# MicroMod-Ethernet-Function-Board.net
KiCad netlist of a schematic drawn in EAGLE
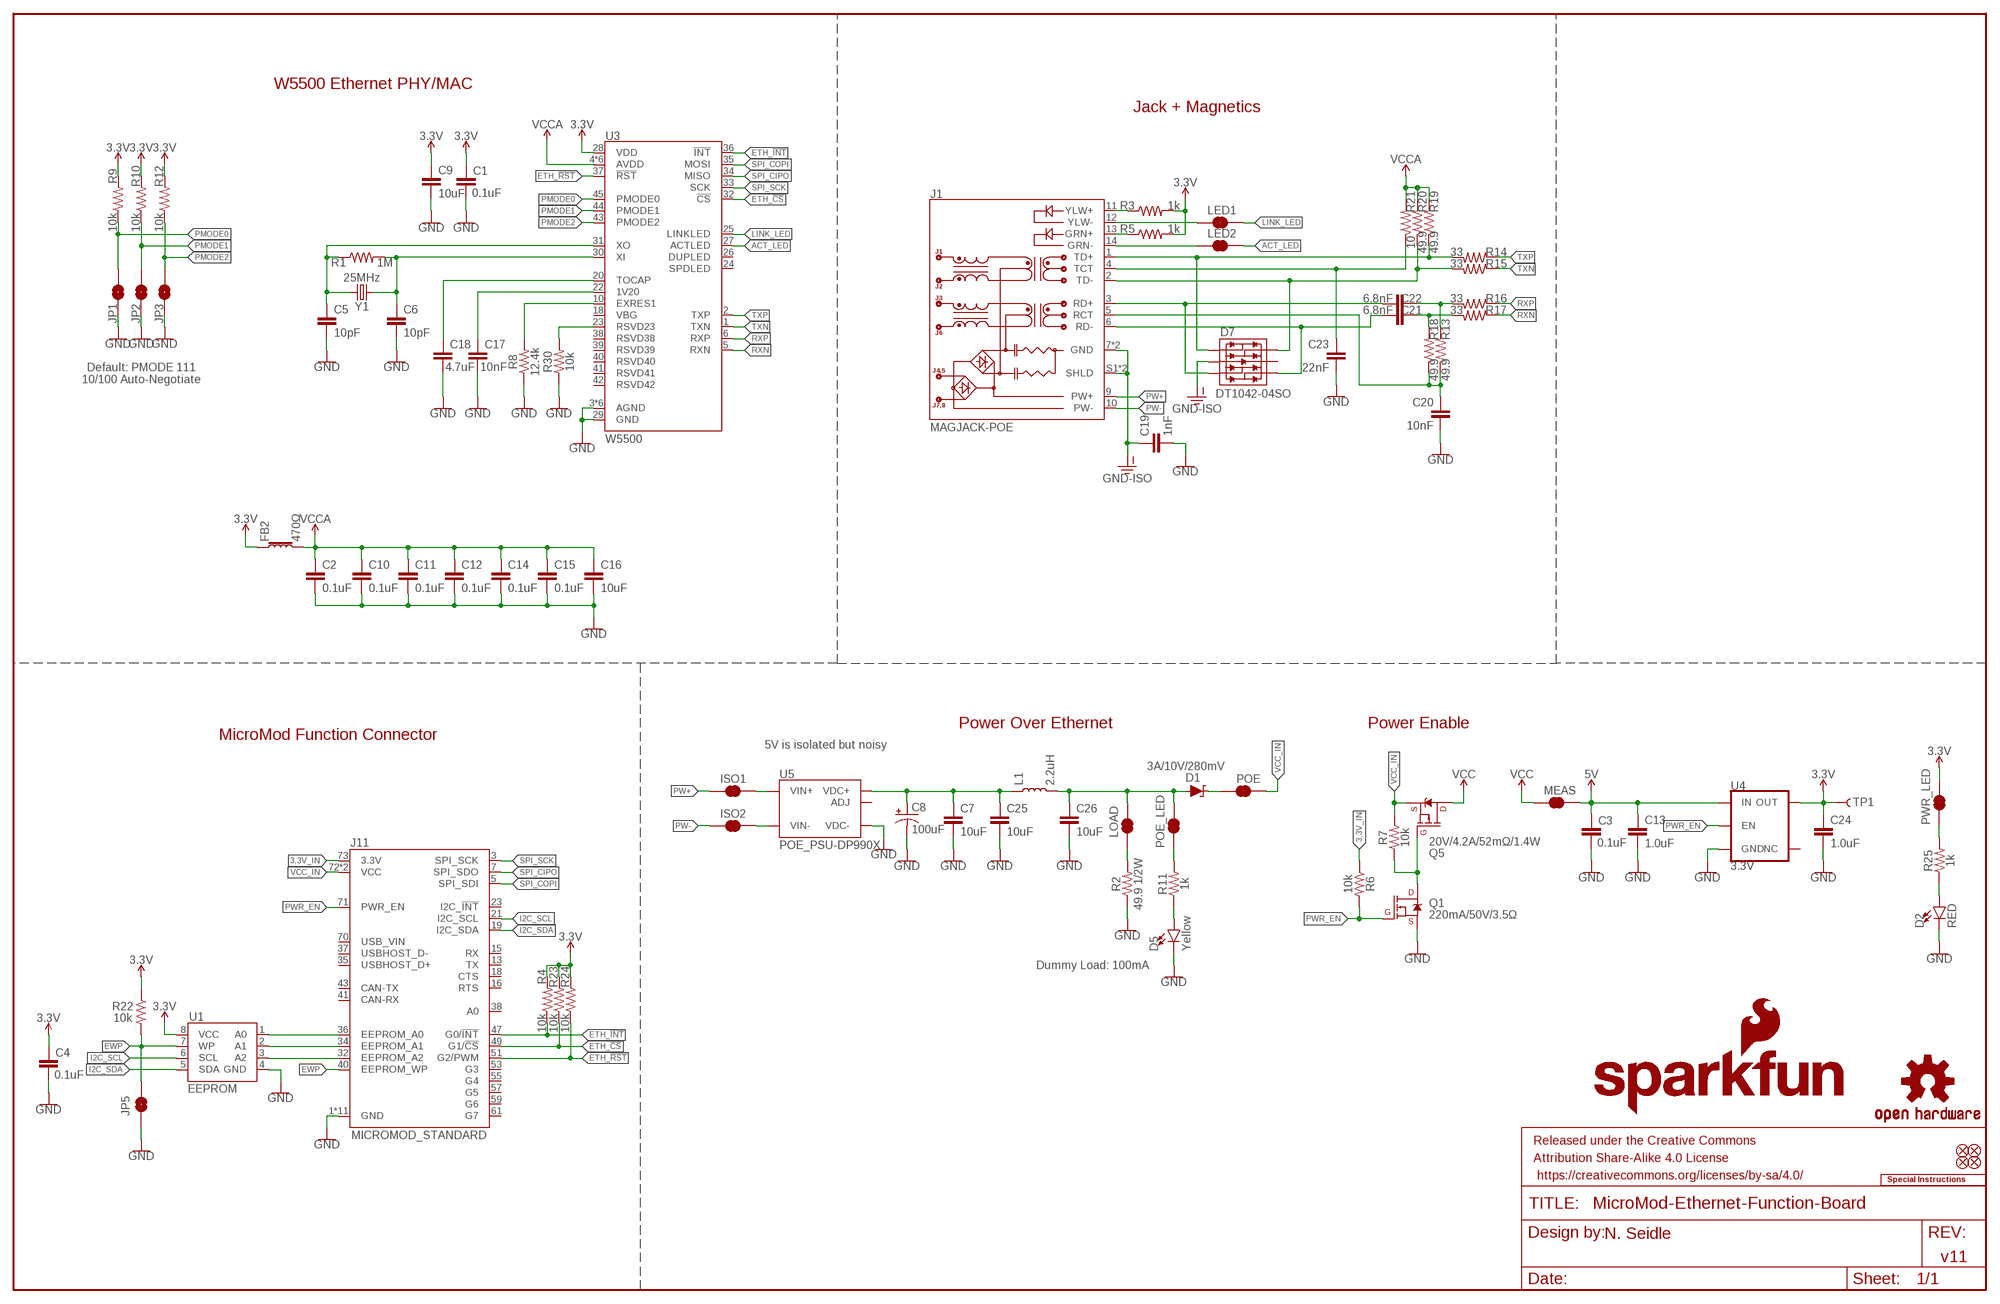
[diagram p0: schematic, sheet 1]

(export (version "E")
  (design (tool "Eeschema 10.0.6"))
  (components
    (comp (ref "C1")
      (value "0.1uF")
      (footprint "eagle-import:0603")
      (libsource (lib "eagle-import") (part "0.1UF-0603-25V-(+80/-20%)"))
    )
    (comp (ref "C2")
      (value "0.1uF")
      (footprint "eagle-import:0603")
      (libsource (lib "eagle-import") (part "0.1UF-0603-25V-5%"))
    )
    (comp (ref "C3")
      (value "0.1uF")
      (footprint "eagle-import:0603")
      (libsource (lib "eagle-import") (part "0.1UF-0603-25V-(+80/-20%)"))
    )
    (comp (ref "C4")
      (value "0.1uF")
      (footprint "eagle-import:0603")
      (libsource (lib "eagle-import") (part "0.1UF-0603-25V-(+80/-20%)"))
    )
    (comp (ref "C5")
      (value "10pF")
      (footprint "eagle-import:0603")
      (libsource (lib "eagle-import") (part "10PF-0603-50V-5%"))
    )
    (comp (ref "C6")
      (value "10pF")
      (footprint "eagle-import:0603")
      (libsource (lib "eagle-import") (part "10PF-0603-50V-5%"))
    )
    (comp (ref "C7")
      (value "10uF")
      (footprint "eagle-import:0805")
      (libsource (lib "eagle-import") (part "10UF-0805-25V-10%"))
    )
    (comp (ref "C8")
      (value "100uF")
      (footprint "eagle-import:PANASONIC_D")
      (libsource (lib "eagle-import") (part "100UF-POLAR-25V-20%(ELEC)"))
    )
    (comp (ref "C9")
      (value "10uF")
      (footprint "eagle-import:0603")
      (libsource (lib "eagle-import") (part "10UF-0603-6.3V-20%"))
    )
    (comp (ref "C10")
      (value "0.1uF")
      (footprint "eagle-import:0603")
      (libsource (lib "eagle-import") (part "0.1UF-0603-25V-5%"))
    )
    (comp (ref "C11")
      (value "0.1uF")
      (footprint "eagle-import:0603")
      (libsource (lib "eagle-import") (part "0.1UF-0603-25V-5%"))
    )
    (comp (ref "C12")
      (value "0.1uF")
      (footprint "eagle-import:0603")
      (libsource (lib "eagle-import") (part "0.1UF-0603-25V-5%"))
    )
    (comp (ref "C13")
      (value "1.0uF")
      (footprint "eagle-import:0603")
      (libsource (lib "eagle-import") (part "1.0UF-0603-16V-10%"))
    )
    (comp (ref "C14")
      (value "0.1uF")
      (footprint "eagle-import:0603")
      (libsource (lib "eagle-import") (part "0.1UF-0603-25V-5%"))
    )
    (comp (ref "C15")
      (value "0.1uF")
      (footprint "eagle-import:0603")
      (libsource (lib "eagle-import") (part "0.1UF-0603-25V-5%"))
    )
    (comp (ref "C16")
      (value "10uF")
      (footprint "eagle-import:0603")
      (libsource (lib "eagle-import") (part "10UF-0603-6.3V-20%"))
    )
    (comp (ref "C17")
      (value "10nF")
      (footprint "eagle-import:0603")
      (libsource (lib "eagle-import") (part "10NF-0603-50V-10%"))
    )
    (comp (ref "C18")
      (value "4.7uF")
      (footprint "eagle-import:0603")
      (libsource (lib "eagle-import") (part "4.7UF-0603-6.3V-(10%)"))
    )
    (comp (ref "C19")
      (value "1nF")
      (footprint "eagle-import:1206")
      (libsource (lib "eagle-import") (part "1.0NF/1000PF-1206-2KV-10%"))
    )
    (comp (ref "C20")
      (value "10nF")
      (footprint "eagle-import:0603")
      (libsource (lib "eagle-import") (part "10NF-0603-50V-10%"))
    )
    (comp (ref "C21")
      (value "6.8nF")
      (footprint "eagle-import:0603")
      (libsource (lib "eagle-import") (part "6.8NF/6800PF-0603-50V-5%"))
    )
    (comp (ref "C22")
      (value "6.8nF")
      (footprint "eagle-import:0603")
      (libsource (lib "eagle-import") (part "6.8NF/6800PF-0603-50V-5%"))
    )
    (comp (ref "C23")
      (value "22nF")
      (footprint "eagle-import:0603")
      (libsource (lib "eagle-import") (part "22NF/22,000PF-0603-50V-10%"))
    )
    (comp (ref "C24")
      (value "1.0uF")
      (footprint "eagle-import:0603")
      (libsource (lib "eagle-import") (part "1.0UF-0603-16V-10%-X7R"))
    )
    (comp (ref "C25")
      (value "10uF")
      (footprint "eagle-import:0805")
      (libsource (lib "eagle-import") (part "10UF-0805-25V-10%"))
    )
    (comp (ref "C26")
      (value "10uF")
      (footprint "eagle-import:0805")
      (libsource (lib "eagle-import") (part "10UF-0805-25V-10%"))
    )
    (comp (ref "D1")
      (value "3A/10V/280mV")
      (footprint "eagle-import:SOD-323")
      (libsource (lib "eagle-import") (part "DIODE-SCHOTTKY-BAT60A"))
    )
    (comp (ref "D2")
      (value "RED")
      (footprint "eagle-import:LED-0603")
      (libsource (lib "eagle-import") (part "LED-RED0603"))
    )
    (comp (ref "D5")
      (value "Yellow")
      (footprint "eagle-import:LED-0603")
      (libsource (lib "eagle-import") (part "LED-YELLOW0603"))
    )
    (comp (ref "D7")
      (value "DT1042-04SO")
      (footprint "eagle-import:SOT-23-6")
      (libsource (lib "eagle-import") (part "TVS_DIODE_ARRAYSMD"))
    )
    (comp (ref "FB2")
      (value "470Ω")
      (footprint "eagle-import:0603")
      (libsource (lib "eagle-import") (part "FERRITE_BEAD-0603-470Ω-100MHZ-1A-200MILIΩ"))
    )
    (comp (ref "FD1")
      (value "FIDUCIALUFIDUCIAL")
      (footprint "eagle-import:FIDUCIAL-MICRO")
      (libsource (lib "eagle-import") (part "FIDUCIALUFIDUCIAL"))
    )
    (comp (ref "FD2")
      (value "FIDUCIALUFIDUCIAL")
      (footprint "eagle-import:FIDUCIAL-MICRO")
      (libsource (lib "eagle-import") (part "FIDUCIALUFIDUCIAL"))
    )
    (comp (ref "FD3")
      (value "FIDUCIALUFIDUCIAL")
      (footprint "eagle-import:FIDUCIAL-MICRO")
      (libsource (lib "eagle-import") (part "FIDUCIALUFIDUCIAL"))
    )
    (comp (ref "FD4")
      (value "FIDUCIALUFIDUCIAL")
      (footprint "eagle-import:FIDUCIAL-MICRO")
      (libsource (lib "eagle-import") (part "FIDUCIALUFIDUCIAL"))
    )
    (comp (ref "FRAME1")
      (value "FRAME-LEDGER")
      (footprint "eagle-import:CREATIVE_COMMONS")
      (libsource (lib "eagle-import") (part "FRAME-LEDGER"))
    )
    (comp (ref "ISO1")
      (value "JUMPER-COMBO_2_NC_TRACE")
      (footprint "eagle-import:COMBO-JUMPER_2_NC_TRACE")
      (libsource (lib "eagle-import") (part "JUMPER-COMBO_2_NC_TRACE"))
    )
    (comp (ref "ISO2")
      (value "JUMPER-COMBO_2_NC_TRACE")
      (footprint "eagle-import:COMBO-JUMPER_2_NC_TRACE")
      (libsource (lib "eagle-import") (part "JUMPER-COMBO_2_NC_TRACE"))
    )
    (comp (ref "J1")
      (value "MAGJACK-POE")
      (footprint "eagle-import:MAGJACK-SYM_LED")
      (libsource (lib "eagle-import") (part "MAGJACK-POE"))
    )
    (comp (ref "J11")
      (value "MICROMOD_STANDARD")
      (footprint "eagle-import:M.2-CARD-E-22_FUNCTION_STANDARD")
      (libsource (lib "eagle-import") (part "MICROMOD_STANDARD"))
    )
    (comp (ref "JP1")
      (value "JUMPER-SMT_2_NO_SILK")
      (footprint "eagle-import:SMT-JUMPER_2_NO_SILK")
      (libsource (lib "eagle-import") (part "JUMPER-SMT_2_NO_SILK"))
    )
    (comp (ref "JP2")
      (value "JUMPER-SMT_2_NO_SILK")
      (footprint "eagle-import:SMT-JUMPER_2_NO_SILK")
      (libsource (lib "eagle-import") (part "JUMPER-SMT_2_NO_SILK"))
    )
    (comp (ref "JP3")
      (value "JUMPER-SMT_2_NO_SILK")
      (footprint "eagle-import:SMT-JUMPER_2_NO_SILK")
      (libsource (lib "eagle-import") (part "JUMPER-SMT_2_NO_SILK"))
    )
    (comp (ref "JP5")
      (value "JUMPER-SMT_2_NO_SILK")
      (footprint "eagle-import:SMT-JUMPER_2_NO_SILK")
      (libsource (lib "eagle-import") (part "JUMPER-SMT_2_NO_SILK"))
    )
    (comp (ref "L1")
      (value "2.2uH")
      (footprint "eagle-import:0805-WIDE")
      (libsource (lib "eagle-import") (part "INDUCTOR-0805_WIDE-2.2UH"))
    )
    (comp (ref "LED1")
      (value "JUMPER-SMT_2_NC_TRACE_SILK")
      (footprint "eagle-import:SMT-JUMPER_2_NC_TRACE_SILK")
      (libsource (lib "eagle-import") (part "JUMPER-SMT_2_NC_TRACE_SILK"))
    )
    (comp (ref "LED2")
      (value "JUMPER-SMT_2_NC_TRACE_SILK")
      (footprint "eagle-import:SMT-JUMPER_2_NC_TRACE_SILK")
      (libsource (lib "eagle-import") (part "JUMPER-SMT_2_NC_TRACE_SILK"))
    )
    (comp (ref "LOAD")
      (value "JUMPER-SMT_2_NC_TRACE_SILK")
      (footprint "eagle-import:SMT-JUMPER_2_NC_TRACE_SILK")
      (libsource (lib "eagle-import") (part "JUMPER-SMT_2_NC_TRACE_SILK"))
    )
    (comp (ref "LOGO1")
      (value "SFE_LOGO_NAME_FLAME.1_INCH")
      (footprint "eagle-import:SFE_LOGO_NAME_FLAME_.1")
      (libsource (lib "eagle-import") (part "SFE_LOGO_NAME_FLAME.1_INCH"))
    )
    (comp (ref "LOGO2")
      (value "SPECIAL_INSTRUCTIONS-ORDERING")
      (footprint "eagle-import:ORDERING_INSTRUCTIONS")
      (libsource (lib "eagle-import") (part "SPECIAL_INSTRUCTIONS-ORDERING"))
    )
    (comp (ref "LOGO3")
      (value "OSHW-LOGOMINI")
      (footprint "eagle-import:OSHW-LOGO-MINI")
      (libsource (lib "eagle-import") (part "OSHW-LOGOMINI"))
    )
    (comp (ref "MEAS")
      (value "JUMPER-COMBO_2_NC_TRACE")
      (footprint "eagle-import:COMBO-JUMPER_2_NC_TRACE")
      (libsource (lib "eagle-import") (part "JUMPER-COMBO_2_NC_TRACE"))
    )
    (comp (ref "POE")
      (value "JUMPER-SMT_2_NC_TRACE_SILK")
      (footprint "eagle-import:SMT-JUMPER_2_NC_TRACE_SILK")
      (libsource (lib "eagle-import") (part "JUMPER-SMT_2_NC_TRACE_SILK"))
    )
    (comp (ref "POE_LED")
      (value "JUMPER-SMT_2_NC_TRACE_SILK")
      (footprint "eagle-import:SMT-JUMPER_2_NC_TRACE_SILK")
      (libsource (lib "eagle-import") (part "JUMPER-SMT_2_NC_TRACE_SILK"))
    )
    (comp (ref "PWR_LED")
      (value "JUMPER-SMT_2_NC_TRACE_SILK")
      (footprint "eagle-import:SMT-JUMPER_2_NC_TRACE_SILK")
      (libsource (lib "eagle-import") (part "JUMPER-SMT_2_NC_TRACE_SILK"))
    )
    (comp (ref "Q1")
      (value "220mA/50V/3.5Ω")
      (footprint "eagle-import:SOT23-3")
      (libsource (lib "eagle-import") (part "MOSFET-NCH-BSS138"))
    )
    (comp (ref "Q5")
      (value "20V/4.2A/52mΩ/1.4W")
      (footprint "eagle-import:SOT23-3")
      (libsource (lib "eagle-import") (part "MOSFET_PCH-DMG2305UX-7"))
    )
    (comp (ref "R1")
      (value "1M")
      (footprint "eagle-import:0603")
      (libsource (lib "eagle-import") (part "1MOHM-0603-1/4W-5%"))
    )
    (comp (ref "R2")
      (value "49.9 1/2W")
      (footprint "eagle-import:1206")
      (libsource (lib "eagle-import") (part "49.9OHM-1206-1/2W-1%"))
    )
    (comp (ref "R3")
      (value "1k")
      (footprint "eagle-import:0603")
      (libsource (lib "eagle-import") (part "1KOHM-0603-1/10W-1%"))
    )
    (comp (ref "R4")
      (value "10k")
      (footprint "eagle-import:0603")
      (libsource (lib "eagle-import") (part "10KOHM-0603-1/10W-1%"))
    )
    (comp (ref "R5")
      (value "1k")
      (footprint "eagle-import:0603")
      (libsource (lib "eagle-import") (part "1KOHM-0603-1/10W-1%"))
    )
    (comp (ref "R6")
      (value "10k")
      (footprint "eagle-import:0603")
      (libsource (lib "eagle-import") (part "10KOHM-0603-1/10W-1%"))
    )
    (comp (ref "R7")
      (value "10k")
      (footprint "eagle-import:0603")
      (libsource (lib "eagle-import") (part "10KOHM-0603-1/10W-1%"))
    )
    (comp (ref "R8")
      (value "12.4k")
      (footprint "eagle-import:0603")
      (libsource (lib "eagle-import") (part "12.4KOHM-0603-1/10W-1%"))
    )
    (comp (ref "R9")
      (value "10k")
      (footprint "eagle-import:0603")
      (libsource (lib "eagle-import") (part "10KOHM-0603-1/10W-1%"))
    )
    (comp (ref "R10")
      (value "10k")
      (footprint "eagle-import:0603")
      (libsource (lib "eagle-import") (part "10KOHM-0603-1/10W-1%"))
    )
    (comp (ref "R11")
      (value "1k")
      (footprint "eagle-import:0603")
      (libsource (lib "eagle-import") (part "1KOHM-0603-1/10W-1%"))
    )
    (comp (ref "R12")
      (value "10k")
      (footprint "eagle-import:0603")
      (libsource (lib "eagle-import") (part "10KOHM-0603-1/10W-1%"))
    )
    (comp (ref "R13")
      (value "49.9")
      (footprint "eagle-import:0603")
      (libsource (lib "eagle-import") (part "49.9OHM-0603-1/10W-1%"))
    )
    (comp (ref "R14")
      (value "33")
      (footprint "eagle-import:0603")
      (libsource (lib "eagle-import") (part "33OHM-0603-1/10W-1%"))
    )
    (comp (ref "R15")
      (value "33")
      (footprint "eagle-import:0603")
      (libsource (lib "eagle-import") (part "33OHM-0603-1/10W-1%"))
    )
    (comp (ref "R16")
      (value "33")
      (footprint "eagle-import:0603")
      (libsource (lib "eagle-import") (part "33OHM-0603-1/10W-1%"))
    )
    (comp (ref "R17")
      (value "33")
      (footprint "eagle-import:0603")
      (libsource (lib "eagle-import") (part "33OHM-0603-1/10W-1%"))
    )
    (comp (ref "R18")
      (value "49.9")
      (footprint "eagle-import:0603")
      (libsource (lib "eagle-import") (part "49.9OHM-0603-1/10W-1%"))
    )
    (comp (ref "R19")
      (value "49.9")
      (footprint "eagle-import:0603")
      (libsource (lib "eagle-import") (part "49.9OHM-0603-1/10W-1%"))
    )
    (comp (ref "R20")
      (value "49.9")
      (footprint "eagle-import:0603")
      (libsource (lib "eagle-import") (part "49.9OHM-0603-1/10W-1%"))
    )
    (comp (ref "R21")
      (value "10")
      (footprint "eagle-import:0603")
      (libsource (lib "eagle-import") (part "10OHM-0603-1/10W-1%"))
    )
    (comp (ref "R22")
      (value "10k")
      (footprint "eagle-import:0603")
      (libsource (lib "eagle-import") (part "10KOHM-0603-1/10W-1%"))
    )
    (comp (ref "R23")
      (value "10k")
      (footprint "eagle-import:0603")
      (libsource (lib "eagle-import") (part "10KOHM-0603-1/10W-1%"))
    )
    (comp (ref "R24")
      (value "10k")
      (footprint "eagle-import:0603")
      (libsource (lib "eagle-import") (part "10KOHM-0603-1/10W-1%"))
    )
    (comp (ref "R25")
      (value "1k")
      (footprint "eagle-import:0603")
      (libsource (lib "eagle-import") (part "1KOHM-0603-1/10W-1%"))
    )
    (comp (ref "R30")
      (value "10k")
      (footprint "eagle-import:0603")
      (libsource (lib "eagle-import") (part "10KOHM-0603-1/10W-1%"))
    )
    (comp (ref "TP1")
      (value "TEST-POINT3X4")
      (footprint "eagle-import:PAD.03X.04")
      (libsource (lib "eagle-import") (part "TEST-POINT3X4"))
    )
    (comp (ref "U1")
      (value "EEPROM")
      (footprint "eagle-import:SO08")
      (libsource (lib "eagle-import") (part "EEPROM-I2C512K"))
    )
    (comp (ref "U3")
      (value "W5500")
      (footprint "eagle-import:LQFP-48")
      (libsource (lib "eagle-import") (part "W5500"))
    )
    (comp (ref "U4")
      (value "3.3V")
      (footprint "eagle-import:SOT23-5")
      (libsource (lib "eagle-import") (part "V_REG_AP2112K-3.3V"))
    )
    (comp (ref "U5")
      (value "POE_PSU-DP990X")
      (footprint "eagle-import:DP990X")
      (libsource (lib "eagle-import") (part "POE_PSU-DP990X"))
    )
    (comp (ref "Y1")
      (value "25MHz")
      (footprint "eagle-import:CRYSTAL-SMD-2.0X1.6MM")
      (libsource (lib "eagle-import") (part "CRYSTAL-25MHZ-SMD-2.0X1.6MM"))
    )
  )
  (nets
    (net (code "1") (name "/ETH_~{CS}") (class "Default")
      (node (ref "J11") (pin "49") (pinfunction "G1/~{CS}_49") (pintype "bidirectional"))
      (node (ref "R23") (pin "1") (pinfunction "1_1") (pintype "passive"))
      (node (ref "U3") (pin "32") (pinfunction "~{CS}_32") (pintype "bidirectional"))
    )
    (net (code "2") (name "/ETH_~{INT}") (class "Default")
      (node (ref "J11") (pin "47") (pinfunction "G0/~{INT}_47") (pintype "bidirectional"))
      (node (ref "R4") (pin "1") (pinfunction "1_1") (pintype "passive"))
      (node (ref "U3") (pin "36") (pinfunction "~{INT}_36") (pintype "bidirectional"))
    )
    (net (code "3") (name "/ETH_~{RST}") (class "Default")
      (node (ref "J11") (pin "51") (pinfunction "G2/PWM_51") (pintype "bidirectional"))
      (node (ref "R24") (pin "1") (pinfunction "1_1") (pintype "passive"))
      (node (ref "U3") (pin "37") (pinfunction "~{RST}_37") (pintype "bidirectional"))
    )
    (net (code "4") (name "3.3V") (class "Default")
      (node (ref "C1") (pin "1") (pinfunction "1_1") (pintype "passive"))
      (node (ref "C24") (pin "1") (pinfunction "1_1") (pintype "passive"))
      (node (ref "C4") (pin "1") (pinfunction "1_1") (pintype "passive"))
      (node (ref "C9") (pin "1") (pinfunction "1_1") (pintype "passive"))
      (node (ref "FB2") (pin "1") (pinfunction "1_1") (pintype "passive"))
      (node (ref "PWR_LED") (pin "2") (pinfunction "2_2") (pintype "passive"))
      (node (ref "R10") (pin "2") (pinfunction "2_2") (pintype "passive"))
      (node (ref "R12") (pin "2") (pinfunction "2_2") (pintype "passive"))
      (node (ref "R22") (pin "1") (pinfunction "1_1") (pintype "passive"))
      (node (ref "R23") (pin "2") (pinfunction "2_2") (pintype "passive"))
      (node (ref "R24") (pin "2") (pinfunction "2_2") (pintype "passive"))
      (node (ref "R3") (pin "2") (pinfunction "2_2") (pintype "passive"))
      (node (ref "R4") (pin "2") (pinfunction "2_2") (pintype "passive"))
      (node (ref "R5") (pin "2") (pinfunction "2_2") (pintype "passive"))
      (node (ref "R9") (pin "2") (pinfunction "2_2") (pintype "passive"))
      (node (ref "TP1") (pin "1") (pinfunction "1_1") (pintype "bidirectional"))
      (node (ref "U1") (pin "8") (pinfunction "VCC_8") (pintype "power_in"))
      (node (ref "U3") (pin "28") (pinfunction "VDD_28") (pintype "bidirectional"))
      (node (ref "U4") (pin "5") (pinfunction "OUT_5") (pintype "passive"))
    )
    (net (code "5") (name "3.3V_IN") (class "Default")
      (node (ref "J11") (pin "73") (pinfunction "3.3V_73") (pintype "bidirectional"))
      (node (ref "R6") (pin "1") (pinfunction "1_1") (pintype "passive"))
    )
    (net (code "6") (name "5V") (class "Default")
      (node (ref "C13") (pin "1") (pinfunction "1_1") (pintype "passive"))
      (node (ref "C3") (pin "1") (pinfunction "1_1") (pintype "passive"))
      (node (ref "MEAS") (pin "2") (pinfunction "2_2") (pintype "passive"))
      (node (ref "MEAS") (pin "4") (pinfunction "2_4") (pintype "passive"))
      (node (ref "U4") (pin "1") (pinfunction "IN_1") (pintype "input"))
    )
    (net (code "7") (name "ACT_LED") (class "Default")
      (node (ref "LED2") (pin "2") (pinfunction "2_2") (pintype "passive"))
      (node (ref "U3") (pin "27") (pinfunction "ACTLED_27") (pintype "bidirectional"))
    )
    (net (code "8") (name "EWP") (class "Default")
      (node (ref "J11") (pin "40") (pinfunction "EEPROM_WP_40") (pintype "bidirectional"))
      (node (ref "JP5") (pin "2") (pinfunction "2_2") (pintype "passive"))
      (node (ref "R22") (pin "2") (pinfunction "2_2") (pintype "passive"))
      (node (ref "U1") (pin "7") (pinfunction "WP_7") (pintype "bidirectional"))
    )
    (net (code "9") (name "GND") (class "Default")
      (node (ref "C1") (pin "2") (pinfunction "2_2") (pintype "passive"))
      (node (ref "C10") (pin "2") (pinfunction "2_2") (pintype "passive"))
      (node (ref "C11") (pin "2") (pinfunction "2_2") (pintype "passive"))
      (node (ref "C12") (pin "2") (pinfunction "2_2") (pintype "passive"))
      (node (ref "C13") (pin "2") (pinfunction "2_2") (pintype "passive"))
      (node (ref "C14") (pin "2") (pinfunction "2_2") (pintype "passive"))
      (node (ref "C15") (pin "2") (pinfunction "2_2") (pintype "passive"))
      (node (ref "C16") (pin "2") (pinfunction "2_2") (pintype "passive"))
      (node (ref "C17") (pin "2") (pinfunction "2_2") (pintype "passive"))
      (node (ref "C18") (pin "2") (pinfunction "2_2") (pintype "passive"))
      (node (ref "C19") (pin "2") (pinfunction "2_2") (pintype "passive"))
      (node (ref "C2") (pin "2") (pinfunction "2_2") (pintype "passive"))
      (node (ref "C20") (pin "2") (pinfunction "2_2") (pintype "passive"))
      (node (ref "C23") (pin "2") (pinfunction "2_2") (pintype "passive"))
      (node (ref "C24") (pin "2") (pinfunction "2_2") (pintype "passive"))
      (node (ref "C25") (pin "2") (pinfunction "2_2") (pintype "passive"))
      (node (ref "C26") (pin "2") (pinfunction "2_2") (pintype "passive"))
      (node (ref "C3") (pin "2") (pinfunction "2_2") (pintype "passive"))
      (node (ref "C4") (pin "2") (pinfunction "2_2") (pintype "passive"))
      (node (ref "C5") (pin "2") (pinfunction "2_2") (pintype "passive"))
      (node (ref "C6") (pin "2") (pinfunction "2_2") (pintype "passive"))
      (node (ref "C7") (pin "2") (pinfunction "2_2") (pintype "passive"))
      (node (ref "C8") (pin "-") (pinfunction "-_-") (pintype "passive"))
      (node (ref "C9") (pin "2") (pinfunction "2_2") (pintype "passive"))
      (node (ref "D2") (pin "C") (pinfunction "C_C") (pintype "passive"))
      (node (ref "D5") (pin "C") (pinfunction "C_C") (pintype "passive"))
      (node (ref "J11") (pin "1") (pinfunction "GND_1") (pintype "bidirectional"))
      (node (ref "J11") (pin "33") (pinfunction "GND_33") (pintype "bidirectional"))
      (node (ref "J11") (pin "39") (pinfunction "GND_39") (pintype "bidirectional"))
      (node (ref "J11") (pin "45") (pinfunction "GND_45") (pintype "bidirectional"))
      (node (ref "J11") (pin "75") (pinfunction "GND_75") (pintype "bidirectional"))
      (node (ref "J11") (pin "GND1") (pinfunction "GND_GND1") (pintype "bidirectional"))
      (node (ref "J11") (pin "GND2") (pinfunction "GND_GND2") (pintype "bidirectional"))
      (node (ref "J11") (pin "GND3") (pinfunction "GND_GND3") (pintype "bidirectional"))
      (node (ref "J11") (pin "GND4") (pinfunction "GND_GND4") (pintype "bidirectional"))
      (node (ref "J11") (pin "GND5") (pinfunction "GND_GND5") (pintype "bidirectional"))
      (node (ref "J11") (pin "GND6") (pinfunction "GND_GND6") (pintype "bidirectional"))
      (node (ref "JP1") (pin "1") (pinfunction "1_1") (pintype "passive"))
      (node (ref "JP2") (pin "1") (pinfunction "1_1") (pintype "passive"))
      (node (ref "JP3") (pin "1") (pinfunction "1_1") (pintype "passive"))
      (node (ref "JP5") (pin "1") (pinfunction "1_1") (pintype "passive"))
      (node (ref "Q1") (pin "2") (pinfunction "S_2") (pintype "bidirectional"))
      (node (ref "R2") (pin "1") (pinfunction "1_1") (pintype "passive"))
      (node (ref "R30") (pin "1") (pinfunction "1_1") (pintype "passive"))
      (node (ref "R8") (pin "1") (pinfunction "1_1") (pintype "passive"))
      (node (ref "U1") (pin "4") (pinfunction "GND_4") (pintype "power_in"))
      (node (ref "U3") (pin "14") (pinfunction "AGND_14") (pintype "bidirectional"))
      (node (ref "U3") (pin "16") (pinfunction "AGND_16") (pintype "bidirectional"))
      (node (ref "U3") (pin "19") (pinfunction "AGND_19") (pintype "bidirectional"))
      (node (ref "U3") (pin "29") (pinfunction "GND_29") (pintype "bidirectional"))
      (node (ref "U3") (pin "3") (pinfunction "AGND_3") (pintype "bidirectional"))
      (node (ref "U3") (pin "48") (pinfunction "AGND_48") (pintype "bidirectional"))
      (node (ref "U3") (pin "9") (pinfunction "AGND_9") (pintype "bidirectional"))
      (node (ref "U4") (pin "2") (pinfunction "GND_2") (pintype "input"))
      (node (ref "U5") (pin "3") (pinfunction "VDC-_3") (pintype "bidirectional"))
    )
    (net (code "10") (name "GND-ISO") (class "Default")
      (node (ref "C19") (pin "1") (pinfunction "1_1") (pintype "passive"))
      (node (ref "D7") (pin "2") (pinfunction "VSS_2") (pintype "bidirectional"))
      (node (ref "J1") (pin "7") (pinfunction "GND_7") (pintype "bidirectional"))
      (node (ref "J1") (pin "8") (pinfunction "GND_8") (pintype "bidirectional"))
      (node (ref "J1") (pin "S1") (pinfunction "SHLD_S1") (pintype "bidirectional"))
      (node (ref "J1") (pin "S2") (pinfunction "SHLD_S2") (pintype "bidirectional"))
    )
    (net (code "11") (name "I2C_SCL") (class "Default")
      (node (ref "J11") (pin "21") (pinfunction "I2C_SCL_21") (pintype "bidirectional"))
      (node (ref "U1") (pin "6") (pinfunction "SCL_6") (pintype "bidirectional"))
    )
    (net (code "12") (name "I2C_SDA") (class "Default")
      (node (ref "J11") (pin "19") (pinfunction "I2C_SDA_19") (pintype "bidirectional"))
      (node (ref "U1") (pin "5") (pinfunction "SDA_5") (pintype "bidirectional"))
    )
    (net (code "13") (name "LINK_LED") (class "Default")
      (node (ref "LED1") (pin "2") (pinfunction "2_2") (pintype "passive"))
      (node (ref "U3") (pin "25") (pinfunction "LINKLED_25") (pintype "bidirectional"))
    )
    (net (code "14") (name "Net-(C21-Pad1)") (class "Default")
      (node (ref "C21") (pin "1") (pinfunction "1_1") (pintype "passive"))
      (node (ref "R17") (pin "2") (pinfunction "2_2") (pintype "passive"))
      (node (ref "R18") (pin "2") (pinfunction "2_2") (pintype "passive"))
    )
    (net (code "15") (name "Net-(C22-Pad1)") (class "Default")
      (node (ref "C22") (pin "1") (pinfunction "1_1") (pintype "passive"))
      (node (ref "R13") (pin "2") (pinfunction "2_2") (pintype "passive"))
      (node (ref "R16") (pin "2") (pinfunction "2_2") (pintype "passive"))
    )
    (net (code "16") (name "Net-(C25-Pad1)") (class "Default")
      (node (ref "C25") (pin "1") (pinfunction "1_1") (pintype "passive"))
      (node (ref "C7") (pin "1") (pinfunction "1_1") (pintype "passive"))
      (node (ref "C8") (pin "+") (pinfunction "+_+") (pintype "passive"))
      (node (ref "L1") (pin "1") (pinfunction "1_1") (pintype "passive"))
      (node (ref "U5") (pin "1") (pinfunction "VDC+_1") (pintype "bidirectional"))
      (node (ref "U5") (pin "2") (pinfunction "VDC+_2") (pintype "bidirectional"))
    )
    (net (code "17") (name "Net-(C26-Pad1)") (class "Default")
      (node (ref "C26") (pin "1") (pinfunction "1_1") (pintype "passive"))
      (node (ref "D1") (pin "A") (pinfunction "A_A") (pintype "passive"))
      (node (ref "L1") (pin "2") (pinfunction "2_2") (pintype "passive"))
      (node (ref "LOAD") (pin "2") (pinfunction "2_2") (pintype "passive"))
      (node (ref "POE_LED") (pin "2") (pinfunction "2_2") (pintype "passive"))
    )
    (net (code "18") (name "Net-(D1-PadC)") (class "Default")
      (node (ref "D1") (pin "C") (pinfunction "C_C") (pintype "passive"))
      (node (ref "POE") (pin "1") (pinfunction "1_1") (pintype "passive"))
    )
    (net (code "19") (name "Net-(D2-PadA)") (class "Default")
      (node (ref "D2") (pin "A") (pinfunction "A_A") (pintype "passive"))
      (node (ref "R25") (pin "1") (pinfunction "1_1") (pintype "passive"))
    )
    (net (code "20") (name "Net-(D5-PadA)") (class "Default")
      (node (ref "D5") (pin "A") (pinfunction "A_A") (pintype "passive"))
      (node (ref "R11") (pin "1") (pinfunction "1_1") (pintype "passive"))
    )
    (net (code "21") (name "Net-(D7-IO1)") (class "Default")
      (node (ref "D7") (pin "1") (pinfunction "IO1_1") (pintype "bidirectional"))
      (node (ref "J1") (pin "1") (pinfunction "TD+_1") (pintype "bidirectional"))
      (node (ref "R14") (pin "2") (pinfunction "2_2") (pintype "passive"))
      (node (ref "R19") (pin "1") (pinfunction "1_1") (pintype "passive"))
    )
    (net (code "22") (name "Net-(D7-IO2)") (class "Default")
      (node (ref "C22") (pin "2") (pinfunction "2_2") (pintype "passive"))
      (node (ref "D7") (pin "3") (pinfunction "IO2_3") (pintype "bidirectional"))
      (node (ref "J1") (pin "3") (pinfunction "RD+_3") (pintype "bidirectional"))
    )
    (net (code "23") (name "Net-(D7-IO3)") (class "Default")
      (node (ref "C21") (pin "2") (pinfunction "2_2") (pintype "passive"))
      (node (ref "D7") (pin "4") (pinfunction "IO3_4") (pintype "bidirectional"))
      (node (ref "J1") (pin "6") (pinfunction "RD-_6") (pintype "bidirectional"))
    )
    (net (code "24") (name "Net-(D7-IO4)") (class "Default")
      (node (ref "D7") (pin "6") (pinfunction "IO4_6") (pintype "bidirectional"))
      (node (ref "J1") (pin "2") (pinfunction "TD-_2") (pintype "bidirectional"))
      (node (ref "R15") (pin "2") (pinfunction "2_2") (pintype "passive"))
      (node (ref "R20") (pin "1") (pinfunction "1_1") (pintype "passive"))
    )
    (net (code "25") (name "Net-(ISO1-2-Pad4)") (class "Default")
      (node (ref "ISO1") (pin "2") (pinfunction "2_2") (pintype "passive"))
      (node (ref "ISO1") (pin "4") (pinfunction "2_4") (pintype "passive"))
      (node (ref "U5") (pin "5") (pinfunction "VIN+_5") (pintype "bidirectional"))
      (node (ref "U5") (pin "6") (pinfunction "VIN+_6") (pintype "bidirectional"))
    )
    (net (code "26") (name "Net-(ISO2-2-Pad4)") (class "Default")
      (node (ref "ISO2") (pin "2") (pinfunction "2_2") (pintype "passive"))
      (node (ref "ISO2") (pin "4") (pinfunction "2_4") (pintype "passive"))
      (node (ref "U5") (pin "7") (pinfunction "VIN-_7") (pintype "bidirectional"))
      (node (ref "U5") (pin "8") (pinfunction "VIN-_8") (pintype "bidirectional"))
    )
    (net (code "27") (name "Net-(J1-GRN+)") (class "Default")
      (node (ref "J1") (pin "13") (pinfunction "GRN+_13") (pintype "bidirectional"))
      (node (ref "R5") (pin "1") (pinfunction "1_1") (pintype "passive"))
    )
    (net (code "28") (name "Net-(J1-GRN-)") (class "Default")
      (node (ref "J1") (pin "14") (pinfunction "GRN-_14") (pintype "bidirectional"))
      (node (ref "LED2") (pin "1") (pinfunction "1_1") (pintype "passive"))
    )
    (net (code "29") (name "Net-(J1-RCT)") (class "Default")
      (node (ref "C20") (pin "1") (pinfunction "1_1") (pintype "passive"))
      (node (ref "J1") (pin "5") (pinfunction "RCT_5") (pintype "bidirectional"))
      (node (ref "R13") (pin "1") (pinfunction "1_1") (pintype "passive"))
      (node (ref "R18") (pin "1") (pinfunction "1_1") (pintype "passive"))
    )
    (net (code "30") (name "Net-(J1-TCT)") (class "Default")
      (node (ref "C23") (pin "1") (pinfunction "1_1") (pintype "passive"))
      (node (ref "J1") (pin "4") (pinfunction "TCT_4") (pintype "bidirectional"))
      (node (ref "R21") (pin "1") (pinfunction "1_1") (pintype "passive"))
    )
    (net (code "31") (name "Net-(J1-YLW+)") (class "Default")
      (node (ref "J1") (pin "11") (pinfunction "YLW+_11") (pintype "bidirectional"))
      (node (ref "R3") (pin "1") (pinfunction "1_1") (pintype "passive"))
    )
    (net (code "32") (name "Net-(J1-YLW-)") (class "Default")
      (node (ref "J1") (pin "12") (pinfunction "YLW-_12") (pintype "bidirectional"))
      (node (ref "LED1") (pin "1") (pinfunction "1_1") (pintype "passive"))
    )
    (net (code "33") (name "Net-(J11-EEPROM_A0)") (class "Default")
      (node (ref "J11") (pin "36") (pinfunction "EEPROM_A0_36") (pintype "bidirectional"))
      (node (ref "U1") (pin "1") (pinfunction "A0_1") (pintype "bidirectional"))
    )
    (net (code "34") (name "Net-(J11-EEPROM_A1)") (class "Default")
      (node (ref "J11") (pin "34") (pinfunction "EEPROM_A1_34") (pintype "bidirectional"))
      (node (ref "U1") (pin "2") (pinfunction "A1_2") (pintype "bidirectional"))
    )
    (net (code "35") (name "Net-(J11-EEPROM_A2)") (class "Default")
      (node (ref "J11") (pin "32") (pinfunction "EEPROM_A2_32") (pintype "bidirectional"))
      (node (ref "U1") (pin "3") (pinfunction "A2_3") (pintype "bidirectional"))
    )
    (net (code "36") (name "Net-(LOAD-Pad1)") (class "Default")
      (node (ref "LOAD") (pin "1") (pinfunction "1_1") (pintype "passive"))
      (node (ref "R2") (pin "2") (pinfunction "2_2") (pintype "passive"))
    )
    (net (code "37") (name "Net-(POE_LED-Pad1)") (class "Default")
      (node (ref "POE_LED") (pin "1") (pinfunction "1_1") (pintype "passive"))
      (node (ref "R11") (pin "2") (pinfunction "2_2") (pintype "passive"))
    )
    (net (code "38") (name "Net-(PWR_LED-Pad1)") (class "Default")
      (node (ref "PWR_LED") (pin "1") (pinfunction "1_1") (pintype "passive"))
      (node (ref "R25") (pin "2") (pinfunction "2_2") (pintype "passive"))
    )
    (net (code "39") (name "Net-(Q1-D)") (class "Default")
      (node (ref "Q1") (pin "3") (pinfunction "D_3") (pintype "bidirectional"))
      (node (ref "Q5") (pin "1") (pinfunction "G_1") (pintype "bidirectional"))
      (node (ref "R7") (pin "1") (pinfunction "1_1") (pintype "passive"))
    )
    (net (code "40") (name "Net-(U3-1V20)") (class "Default")
      (node (ref "C17") (pin "1") (pinfunction "1_1") (pintype "passive"))
      (node (ref "U3") (pin "22") (pinfunction "1V20_22") (pintype "bidirectional"))
    )
    (net (code "41") (name "Net-(U3-EXRES1)") (class "Default")
      (node (ref "R8") (pin "2") (pinfunction "2_2") (pintype "passive"))
      (node (ref "U3") (pin "10") (pinfunction "EXRES1_10") (pintype "bidirectional"))
    )
    (net (code "42") (name "Net-(U3-RSVD23)") (class "Default")
      (node (ref "R30") (pin "2") (pinfunction "2_2") (pintype "passive"))
      (node (ref "U3") (pin "23") (pinfunction "RSVD23_23") (pintype "bidirectional"))
    )
    (net (code "43") (name "Net-(U3-TOCAP)") (class "Default")
      (node (ref "C18") (pin "1") (pinfunction "1_1") (pintype "passive"))
      (node (ref "U3") (pin "20") (pinfunction "TOCAP_20") (pintype "bidirectional"))
    )
    (net (code "44") (name "Net-(U3-XI)") (class "Default")
      (node (ref "C6") (pin "1") (pinfunction "1_1") (pintype "passive"))
      (node (ref "R1") (pin "2") (pinfunction "2_2") (pintype "passive"))
      (node (ref "U3") (pin "30") (pinfunction "XI_30") (pintype "bidirectional"))
      (node (ref "Y1") (pin "3") (pinfunction "2_3") (pintype "passive"))
    )
    (net (code "45") (name "Net-(U3-XO)") (class "Default")
      (node (ref "C5") (pin "1") (pinfunction "1_1") (pintype "passive"))
      (node (ref "R1") (pin "1") (pinfunction "1_1") (pintype "passive"))
      (node (ref "U3") (pin "31") (pinfunction "XO_31") (pintype "bidirectional"))
      (node (ref "Y1") (pin "1") (pinfunction "1_1") (pintype "passive"))
    )
    (net (code "46") (name "PMODE0") (class "Default")
      (node (ref "JP1") (pin "2") (pinfunction "2_2") (pintype "passive"))
      (node (ref "R9") (pin "1") (pinfunction "1_1") (pintype "passive"))
      (node (ref "U3") (pin "45") (pinfunction "PMODE0_45") (pintype "bidirectional"))
    )
    (net (code "47") (name "PMODE1") (class "Default")
      (node (ref "JP2") (pin "2") (pinfunction "2_2") (pintype "passive"))
      (node (ref "R10") (pin "1") (pinfunction "1_1") (pintype "passive"))
      (node (ref "U3") (pin "44") (pinfunction "PMODE1_44") (pintype "bidirectional"))
    )
    (net (code "48") (name "PMODE2") (class "Default")
      (node (ref "JP3") (pin "2") (pinfunction "2_2") (pintype "passive"))
      (node (ref "R12") (pin "1") (pinfunction "1_1") (pintype "passive"))
      (node (ref "U3") (pin "43") (pinfunction "PMODE2_43") (pintype "bidirectional"))
    )
    (net (code "49") (name "PW+") (class "Default")
      (node (ref "ISO1") (pin "1") (pinfunction "1_1") (pintype "passive"))
      (node (ref "ISO1") (pin "3") (pinfunction "1_3") (pintype "passive"))
      (node (ref "J1") (pin "9") (pinfunction "PW+_9") (pintype "bidirectional"))
    )
    (net (code "50") (name "PW-") (class "Default")
      (node (ref "ISO2") (pin "1") (pinfunction "1_1") (pintype "passive"))
      (node (ref "ISO2") (pin "3") (pinfunction "1_3") (pintype "passive"))
      (node (ref "J1") (pin "10") (pinfunction "PW-_10") (pintype "bidirectional"))
    )
    (net (code "51") (name "PWR_EN") (class "Default")
      (node (ref "J11") (pin "71") (pinfunction "PWR_EN_71") (pintype "bidirectional"))
      (node (ref "Q1") (pin "1") (pinfunction "G_1") (pintype "bidirectional"))
      (node (ref "R6") (pin "2") (pinfunction "2_2") (pintype "passive"))
      (node (ref "U4") (pin "3") (pinfunction "EN_3") (pintype "input"))
    )
    (net (code "52") (name "RXN") (class "Default")
      (node (ref "R17") (pin "1") (pinfunction "1_1") (pintype "passive"))
      (node (ref "U3") (pin "5") (pinfunction "RXN_5") (pintype "bidirectional"))
    )
    (net (code "53") (name "RXP") (class "Default")
      (node (ref "R16") (pin "1") (pinfunction "1_1") (pintype "passive"))
      (node (ref "U3") (pin "6") (pinfunction "RXP_6") (pintype "bidirectional"))
    )
    (net (code "54") (name "SPI_CIPO") (class "Default")
      (node (ref "J11") (pin "7") (pinfunction "SPI_SDO_7") (pintype "bidirectional"))
      (node (ref "U3") (pin "34") (pinfunction "MISO_34") (pintype "bidirectional"))
    )
    (net (code "55") (name "SPI_COPI") (class "Default")
      (node (ref "J11") (pin "5") (pinfunction "SPI_SDI_5") (pintype "bidirectional"))
      (node (ref "U3") (pin "35") (pinfunction "MOSI_35") (pintype "bidirectional"))
    )
    (net (code "56") (name "SPI_SCK") (class "Default")
      (node (ref "J11") (pin "3") (pinfunction "SPI_SCK_3") (pintype "bidirectional"))
      (node (ref "U3") (pin "33") (pinfunction "SCK_33") (pintype "bidirectional"))
    )
    (net (code "57") (name "TXN") (class "Default")
      (node (ref "R15") (pin "1") (pinfunction "1_1") (pintype "passive"))
      (node (ref "U3") (pin "1") (pinfunction "TXN_1") (pintype "bidirectional"))
    )
    (net (code "58") (name "TXP") (class "Default")
      (node (ref "R14") (pin "1") (pinfunction "1_1") (pintype "passive"))
      (node (ref "U3") (pin "2") (pinfunction "TXP_2") (pintype "bidirectional"))
    )
    (net (code "59") (name "VCC") (class "Default")
      (node (ref "MEAS") (pin "1") (pinfunction "1_1") (pintype "passive"))
      (node (ref "MEAS") (pin "3") (pinfunction "1_3") (pintype "passive"))
      (node (ref "Q5") (pin "3") (pinfunction "D_3") (pintype "bidirectional"))
    )
    (net (code "60") (name "VCCA") (class "Default")
      (node (ref "C10") (pin "1") (pinfunction "1_1") (pintype "passive"))
      (node (ref "C11") (pin "1") (pinfunction "1_1") (pintype "passive"))
      (node (ref "C12") (pin "1") (pinfunction "1_1") (pintype "passive"))
      (node (ref "C14") (pin "1") (pinfunction "1_1") (pintype "passive"))
      (node (ref "C15") (pin "1") (pinfunction "1_1") (pintype "passive"))
      (node (ref "C16") (pin "1") (pinfunction "1_1") (pintype "passive"))
      (node (ref "C2") (pin "1") (pinfunction "1_1") (pintype "passive"))
      (node (ref "FB2") (pin "2") (pinfunction "2_2") (pintype "passive"))
      (node (ref "R19") (pin "2") (pinfunction "2_2") (pintype "passive"))
      (node (ref "R20") (pin "2") (pinfunction "2_2") (pintype "passive"))
      (node (ref "R21") (pin "2") (pinfunction "2_2") (pintype "passive"))
      (node (ref "U3") (pin "11") (pinfunction "AVDD_11") (pintype "bidirectional"))
      (node (ref "U3") (pin "15") (pinfunction "AVDD_15") (pintype "bidirectional"))
      (node (ref "U3") (pin "17") (pinfunction "AVDD_17") (pintype "bidirectional"))
      (node (ref "U3") (pin "21") (pinfunction "AVDD_21") (pintype "bidirectional"))
      (node (ref "U3") (pin "4") (pinfunction "AVDD_4") (pintype "bidirectional"))
      (node (ref "U3") (pin "8") (pinfunction "AVDD_8") (pintype "bidirectional"))
    )
    (net (code "61") (name "VCC_IN") (class "Default")
      (node (ref "J11") (pin "72") (pinfunction "VCC_72") (pintype "bidirectional"))
      (node (ref "J11") (pin "74") (pinfunction "VCC_74") (pintype "bidirectional"))
      (node (ref "POE") (pin "2") (pinfunction "2_2") (pintype "passive"))
      (node (ref "Q5") (pin "2") (pinfunction "S_2") (pintype "bidirectional"))
      (node (ref "R7") (pin "2") (pinfunction "2_2") (pintype "passive"))
    )
    (net (code "62") (name "unconnected-(D7-VCC-Pad5)") (class "Default")
      (node (ref "D7") (pin "5") (pinfunction "VCC_5") (pintype "bidirectional"))
    )
    (net (code "63") (name "unconnected-(J11-A0-Pad38)") (class "Default")
      (node (ref "J11") (pin "38") (pinfunction "A0_38") (pintype "bidirectional"))
    )
    (net (code "64") (name "unconnected-(J11-CAN-RX-Pad41)") (class "Default")
      (node (ref "J11") (pin "41") (pinfunction "CAN-RX_41") (pintype "bidirectional"))
    )
    (net (code "65") (name "unconnected-(J11-CAN-TX-Pad43)") (class "Default")
      (node (ref "J11") (pin "43") (pinfunction "CAN-TX_43") (pintype "bidirectional"))
    )
    (net (code "66") (name "unconnected-(J11-CTS-Pad18)") (class "Default")
      (node (ref "J11") (pin "18") (pinfunction "CTS_18") (pintype "bidirectional"))
    )
    (net (code "67") (name "unconnected-(J11-G3-Pad53)") (class "Default")
      (node (ref "J11") (pin "53") (pinfunction "G3_53") (pintype "bidirectional"))
    )
    (net (code "68") (name "unconnected-(J11-G4-Pad55)") (class "Default")
      (node (ref "J11") (pin "55") (pinfunction "G4_55") (pintype "bidirectional"))
    )
    (net (code "69") (name "unconnected-(J11-G5-Pad57)") (class "Default")
      (node (ref "J11") (pin "57") (pinfunction "G5_57") (pintype "bidirectional"))
    )
    (net (code "70") (name "unconnected-(J11-G6-Pad59)") (class "Default")
      (node (ref "J11") (pin "59") (pinfunction "G6_59") (pintype "bidirectional"))
    )
    (net (code "71") (name "unconnected-(J11-G7-Pad61)") (class "Default")
      (node (ref "J11") (pin "61") (pinfunction "G7_61") (pintype "bidirectional"))
    )
    (net (code "72") (name "unconnected-(J11-I2C_~{INT}-Pad23)") (class "Default")
      (node (ref "J11") (pin "23") (pinfunction "I2C_~{INT}_23") (pintype "bidirectional"))
    )
    (net (code "73") (name "unconnected-(J11-RTS-Pad16)") (class "Default")
      (node (ref "J11") (pin "16") (pinfunction "RTS_16") (pintype "bidirectional"))
    )
    (net (code "74") (name "unconnected-(J11-RX-Pad15)") (class "Default")
      (node (ref "J11") (pin "15") (pinfunction "RX_15") (pintype "bidirectional"))
    )
    (net (code "75") (name "unconnected-(J11-TX-Pad13)") (class "Default")
      (node (ref "J11") (pin "13") (pinfunction "TX_13") (pintype "bidirectional"))
    )
    (net (code "76") (name "unconnected-(J11-USBHOST_D+-Pad35)") (class "Default")
      (node (ref "J11") (pin "35") (pinfunction "USBHOST_D+_35") (pintype "bidirectional"))
    )
    (net (code "77") (name "unconnected-(J11-USBHOST_D--Pad37)") (class "Default")
      (node (ref "J11") (pin "37") (pinfunction "USBHOST_D-_37") (pintype "bidirectional"))
    )
    (net (code "78") (name "unconnected-(J11-USB_VIN-Pad70)") (class "Default")
      (node (ref "J11") (pin "70") (pinfunction "USB_VIN_70") (pintype "bidirectional"))
    )
    (net (code "79") (name "unconnected-(U3-DUPLED-Pad26)") (class "Default")
      (node (ref "U3") (pin "26") (pinfunction "DUPLED_26") (pintype "bidirectional"))
    )
    (net (code "80") (name "unconnected-(U3-RSVD38-Pad38)") (class "Default")
      (node (ref "U3") (pin "38") (pinfunction "RSVD38_38") (pintype "bidirectional"))
    )
    (net (code "81") (name "unconnected-(U3-RSVD39-Pad39)") (class "Default")
      (node (ref "U3") (pin "39") (pinfunction "RSVD39_39") (pintype "bidirectional"))
    )
    (net (code "82") (name "unconnected-(U3-RSVD40-Pad40)") (class "Default")
      (node (ref "U3") (pin "40") (pinfunction "RSVD40_40") (pintype "bidirectional"))
    )
    (net (code "83") (name "unconnected-(U3-RSVD41-Pad41)") (class "Default")
      (node (ref "U3") (pin "41") (pinfunction "RSVD41_41") (pintype "bidirectional"))
    )
    (net (code "84") (name "unconnected-(U3-RSVD42-Pad42)") (class "Default")
      (node (ref "U3") (pin "42") (pinfunction "RSVD42_42") (pintype "bidirectional"))
    )
    (net (code "85") (name "unconnected-(U3-SPDLED-Pad24)") (class "Default")
      (node (ref "U3") (pin "24") (pinfunction "SPDLED_24") (pintype "bidirectional"))
    )
    (net (code "86") (name "unconnected-(U3-VBG-Pad18)") (class "Default")
      (node (ref "U3") (pin "18") (pinfunction "VBG_18") (pintype "bidirectional"))
    )
    (net (code "87") (name "unconnected-(U4-NC-Pad4)") (class "Default")
      (node (ref "U4") (pin "4") (pinfunction "NC_4") (pintype "no_connect"))
    )
    (net (code "88") (name "unconnected-(U5-ADJ-Pad4)") (class "Default")
      (node (ref "U5") (pin "4") (pinfunction "ADJ_4") (pintype "bidirectional"))
    )
  )
)
